# center_v2.net
KiCad netlist of a schematic drawn in EAGLE
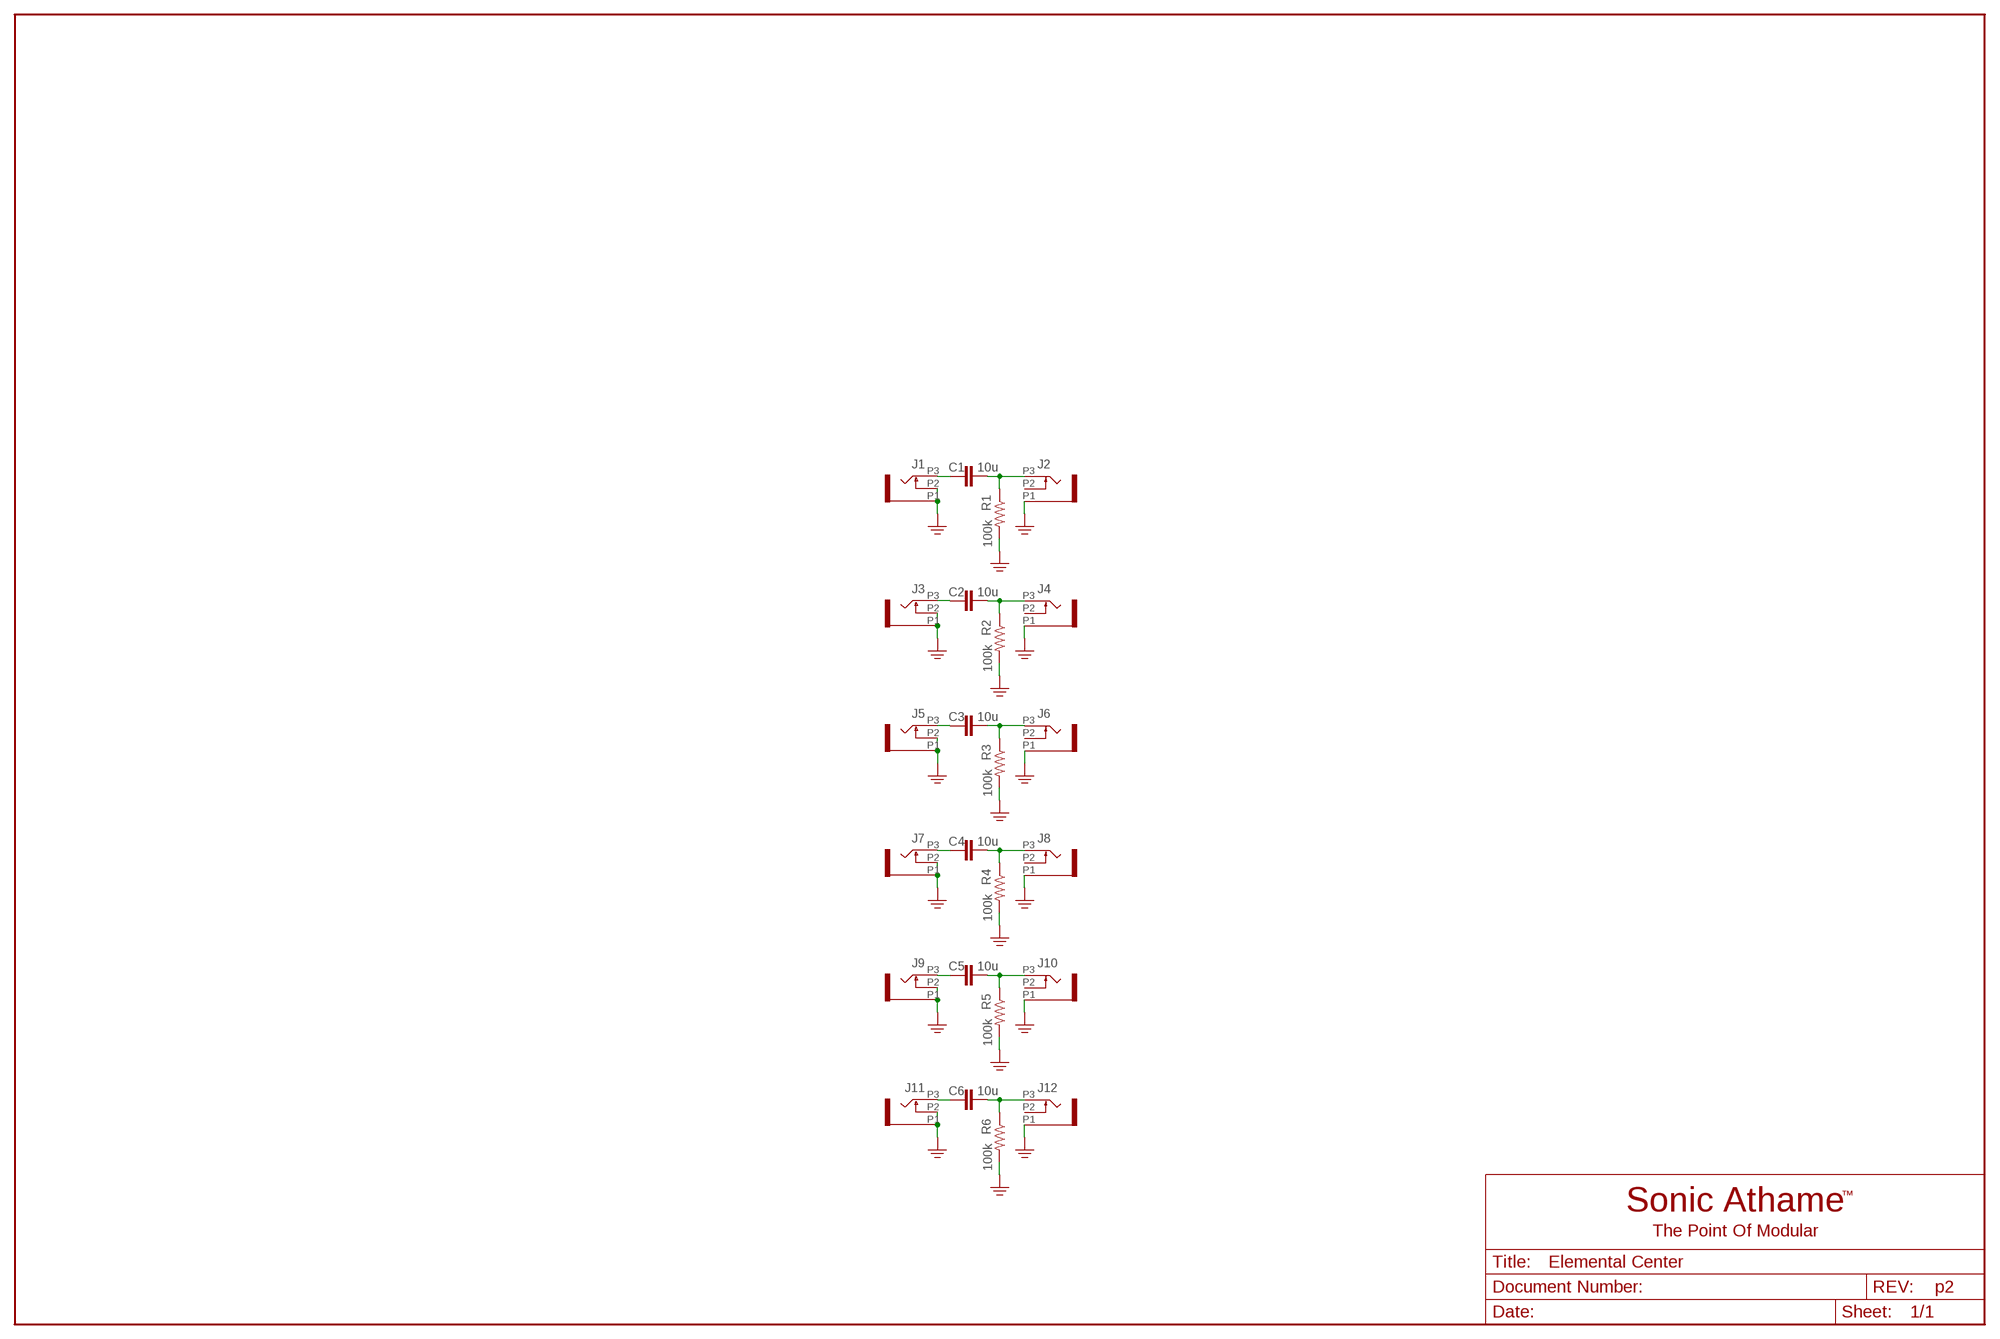
[diagram p0: schematic, sheet 1]

(export (version "E")
  (design (tool "Eeschema 10.0.6"))
  (components
    (comp (ref "C1")
      (value "10u")
      (footprint "eagle-import:C025-024X044")
      (libsource (lib "eagle-import") (part "CAP_NONPOL025-024X044"))
    )
    (comp (ref "C2")
      (value "10u")
      (footprint "eagle-import:C025-024X044")
      (libsource (lib "eagle-import") (part "CAP_NONPOL025-024X044"))
    )
    (comp (ref "C3")
      (value "10u")
      (footprint "eagle-import:C025-024X044")
      (libsource (lib "eagle-import") (part "CAP_NONPOL025-024X044"))
    )
    (comp (ref "C4")
      (value "10u")
      (footprint "eagle-import:C025-024X044")
      (libsource (lib "eagle-import") (part "CAP_NONPOL025-024X044"))
    )
    (comp (ref "C5")
      (value "10u")
      (footprint "eagle-import:C025-024X044")
      (libsource (lib "eagle-import") (part "CAP_NONPOL025-024X044"))
    )
    (comp (ref "C6")
      (value "10u")
      (footprint "eagle-import:C025-024X044")
      (libsource (lib "eagle-import") (part "CAP_NONPOL025-024X044"))
    )
    (comp (ref "J1")
      (value "WQP-PJ398SM6")
      (footprint "eagle-import:WQP_PJ_301M6")
      (libsource (lib "eagle-import") (part "WQP-PJ398SM6"))
    )
    (comp (ref "J2")
      (value "WQP-PJ398SM6")
      (footprint "eagle-import:WQP_PJ_301M6")
      (libsource (lib "eagle-import") (part "WQP-PJ398SM6"))
    )
    (comp (ref "J3")
      (value "WQP-PJ398SM6")
      (footprint "eagle-import:WQP_PJ_301M6")
      (libsource (lib "eagle-import") (part "WQP-PJ398SM6"))
    )
    (comp (ref "J4")
      (value "WQP-PJ398SM6")
      (footprint "eagle-import:WQP_PJ_301M6")
      (libsource (lib "eagle-import") (part "WQP-PJ398SM6"))
    )
    (comp (ref "J5")
      (value "WQP-PJ398SM6")
      (footprint "eagle-import:WQP_PJ_301M6")
      (libsource (lib "eagle-import") (part "WQP-PJ398SM6"))
    )
    (comp (ref "J6")
      (value "WQP-PJ398SM6")
      (footprint "eagle-import:WQP_PJ_301M6")
      (libsource (lib "eagle-import") (part "WQP-PJ398SM6"))
    )
    (comp (ref "J7")
      (value "WQP-PJ398SM6")
      (footprint "eagle-import:WQP_PJ_301M6")
      (libsource (lib "eagle-import") (part "WQP-PJ398SM6"))
    )
    (comp (ref "J8")
      (value "WQP-PJ398SM6")
      (footprint "eagle-import:WQP_PJ_301M6")
      (libsource (lib "eagle-import") (part "WQP-PJ398SM6"))
    )
    (comp (ref "J9")
      (value "WQP-PJ398SM6")
      (footprint "eagle-import:WQP_PJ_301M6")
      (libsource (lib "eagle-import") (part "WQP-PJ398SM6"))
    )
    (comp (ref "J10")
      (value "WQP-PJ398SM6")
      (footprint "eagle-import:WQP_PJ_301M6")
      (libsource (lib "eagle-import") (part "WQP-PJ398SM6"))
    )
    (comp (ref "J11")
      (value "WQP-PJ398SM6")
      (footprint "eagle-import:WQP_PJ_301M6")
      (libsource (lib "eagle-import") (part "WQP-PJ398SM6"))
    )
    (comp (ref "J12")
      (value "WQP-PJ398SM6")
      (footprint "eagle-import:WQP_PJ_301M6")
      (libsource (lib "eagle-import") (part "WQP-PJ398SM6"))
    )
    (comp (ref "R1")
      (value "100k")
      (footprint "eagle-import:0207_2V")
      (libsource (lib "eagle-import") (part "RESISTOR0207/2V"))
    )
    (comp (ref "R2")
      (value "100k")
      (footprint "eagle-import:0207_2V")
      (libsource (lib "eagle-import") (part "RESISTOR0207/2V"))
    )
    (comp (ref "R3")
      (value "100k")
      (footprint "eagle-import:0207_2V")
      (libsource (lib "eagle-import") (part "RESISTOR0207/2V"))
    )
    (comp (ref "R4")
      (value "100k")
      (footprint "eagle-import:0207_2V")
      (libsource (lib "eagle-import") (part "RESISTOR0207/2V"))
    )
    (comp (ref "R5")
      (value "100k")
      (footprint "eagle-import:0207_2V")
      (libsource (lib "eagle-import") (part "RESISTOR0207/2V"))
    )
    (comp (ref "R6")
      (value "100k")
      (footprint "eagle-import:0207_2V")
      (libsource (lib "eagle-import") (part "RESISTOR0207/2V"))
    )
  )
  (nets
    (net (code "1") (name "GND") (class "Default")
      (node (ref "J1") (pin "P1") (pinfunction "1_P1") (pintype "passive"))
      (node (ref "J1") (pin "P2") (pinfunction "2_P2") (pintype "passive"))
      (node (ref "J10") (pin "P1") (pinfunction "1_P1") (pintype "passive"))
      (node (ref "J11") (pin "P1") (pinfunction "1_P1") (pintype "passive"))
      (node (ref "J11") (pin "P2") (pinfunction "2_P2") (pintype "passive"))
      (node (ref "J12") (pin "P1") (pinfunction "1_P1") (pintype "passive"))
      (node (ref "J2") (pin "P1") (pinfunction "1_P1") (pintype "passive"))
      (node (ref "J3") (pin "P1") (pinfunction "1_P1") (pintype "passive"))
      (node (ref "J3") (pin "P2") (pinfunction "2_P2") (pintype "passive"))
      (node (ref "J4") (pin "P1") (pinfunction "1_P1") (pintype "passive"))
      (node (ref "J5") (pin "P1") (pinfunction "1_P1") (pintype "passive"))
      (node (ref "J5") (pin "P2") (pinfunction "2_P2") (pintype "passive"))
      (node (ref "J6") (pin "P1") (pinfunction "1_P1") (pintype "passive"))
      (node (ref "J7") (pin "P1") (pinfunction "1_P1") (pintype "passive"))
      (node (ref "J7") (pin "P2") (pinfunction "2_P2") (pintype "passive"))
      (node (ref "J8") (pin "P1") (pinfunction "1_P1") (pintype "passive"))
      (node (ref "J9") (pin "P1") (pinfunction "1_P1") (pintype "passive"))
      (node (ref "J9") (pin "P2") (pinfunction "2_P2") (pintype "passive"))
      (node (ref "R1") (pin "2") (pinfunction "2_2") (pintype "passive"))
      (node (ref "R2") (pin "2") (pinfunction "2_2") (pintype "passive"))
      (node (ref "R3") (pin "2") (pinfunction "2_2") (pintype "passive"))
      (node (ref "R4") (pin "2") (pinfunction "2_2") (pintype "passive"))
      (node (ref "R5") (pin "2") (pinfunction "2_2") (pintype "passive"))
      (node (ref "R6") (pin "2") (pinfunction "2_2") (pintype "passive"))
    )
    (net (code "2") (name "Net-(J1-3)") (class "Default")
      (node (ref "C1") (pin "1") (pinfunction "1_1") (pintype "passive"))
      (node (ref "J1") (pin "P3") (pinfunction "3_P3") (pintype "passive"))
    )
    (net (code "3") (name "Net-(J2-3)") (class "Default")
      (node (ref "C1") (pin "2") (pinfunction "2_2") (pintype "passive"))
      (node (ref "J2") (pin "P3") (pinfunction "3_P3") (pintype "passive"))
      (node (ref "R1") (pin "1") (pinfunction "1_1") (pintype "passive"))
    )
    (net (code "4") (name "Net-(J3-3)") (class "Default")
      (node (ref "C2") (pin "1") (pinfunction "1_1") (pintype "passive"))
      (node (ref "J3") (pin "P3") (pinfunction "3_P3") (pintype "passive"))
    )
    (net (code "5") (name "Net-(J4-3)") (class "Default")
      (node (ref "C2") (pin "2") (pinfunction "2_2") (pintype "passive"))
      (node (ref "J4") (pin "P3") (pinfunction "3_P3") (pintype "passive"))
      (node (ref "R2") (pin "1") (pinfunction "1_1") (pintype "passive"))
    )
    (net (code "6") (name "Net-(J5-3)") (class "Default")
      (node (ref "C3") (pin "1") (pinfunction "1_1") (pintype "passive"))
      (node (ref "J5") (pin "P3") (pinfunction "3_P3") (pintype "passive"))
    )
    (net (code "7") (name "Net-(J6-3)") (class "Default")
      (node (ref "C3") (pin "2") (pinfunction "2_2") (pintype "passive"))
      (node (ref "J6") (pin "P3") (pinfunction "3_P3") (pintype "passive"))
      (node (ref "R3") (pin "1") (pinfunction "1_1") (pintype "passive"))
    )
    (net (code "8") (name "Net-(J7-3)") (class "Default")
      (node (ref "C4") (pin "1") (pinfunction "1_1") (pintype "passive"))
      (node (ref "J7") (pin "P3") (pinfunction "3_P3") (pintype "passive"))
    )
    (net (code "9") (name "Net-(J8-3)") (class "Default")
      (node (ref "C4") (pin "2") (pinfunction "2_2") (pintype "passive"))
      (node (ref "J8") (pin "P3") (pinfunction "3_P3") (pintype "passive"))
      (node (ref "R4") (pin "1") (pinfunction "1_1") (pintype "passive"))
    )
    (net (code "10") (name "Net-(J9-3)") (class "Default")
      (node (ref "C5") (pin "1") (pinfunction "1_1") (pintype "passive"))
      (node (ref "J9") (pin "P3") (pinfunction "3_P3") (pintype "passive"))
    )
    (net (code "11") (name "Net-(J10-3)") (class "Default")
      (node (ref "C5") (pin "2") (pinfunction "2_2") (pintype "passive"))
      (node (ref "J10") (pin "P3") (pinfunction "3_P3") (pintype "passive"))
      (node (ref "R5") (pin "1") (pinfunction "1_1") (pintype "passive"))
    )
    (net (code "12") (name "Net-(J11-3)") (class "Default")
      (node (ref "C6") (pin "1") (pinfunction "1_1") (pintype "passive"))
      (node (ref "J11") (pin "P3") (pinfunction "3_P3") (pintype "passive"))
    )
    (net (code "13") (name "Net-(J12-3)") (class "Default")
      (node (ref "C6") (pin "2") (pinfunction "2_2") (pintype "passive"))
      (node (ref "J12") (pin "P3") (pinfunction "3_P3") (pintype "passive"))
      (node (ref "R6") (pin "1") (pinfunction "1_1") (pintype "passive"))
    )
    (net (code "14") (name "unconnected-(J2-2-PadP2)") (class "Default")
      (node (ref "J2") (pin "P2") (pinfunction "2_P2") (pintype "passive"))
    )
    (net (code "15") (name "unconnected-(J4-2-PadP2)") (class "Default")
      (node (ref "J4") (pin "P2") (pinfunction "2_P2") (pintype "passive"))
    )
    (net (code "16") (name "unconnected-(J6-2-PadP2)") (class "Default")
      (node (ref "J6") (pin "P2") (pinfunction "2_P2") (pintype "passive"))
    )
    (net (code "17") (name "unconnected-(J8-2-PadP2)") (class "Default")
      (node (ref "J8") (pin "P2") (pinfunction "2_P2") (pintype "passive"))
    )
    (net (code "18") (name "unconnected-(J10-2-PadP2)") (class "Default")
      (node (ref "J10") (pin "P2") (pinfunction "2_P2") (pintype "passive"))
    )
    (net (code "19") (name "unconnected-(J12-2-PadP2)") (class "Default")
      (node (ref "J12") (pin "P2") (pinfunction "2_P2") (pintype "passive"))
    )
  )
)
